# Microcontroller.net
KiCad netlist of a schematic drawn in Altium Designer
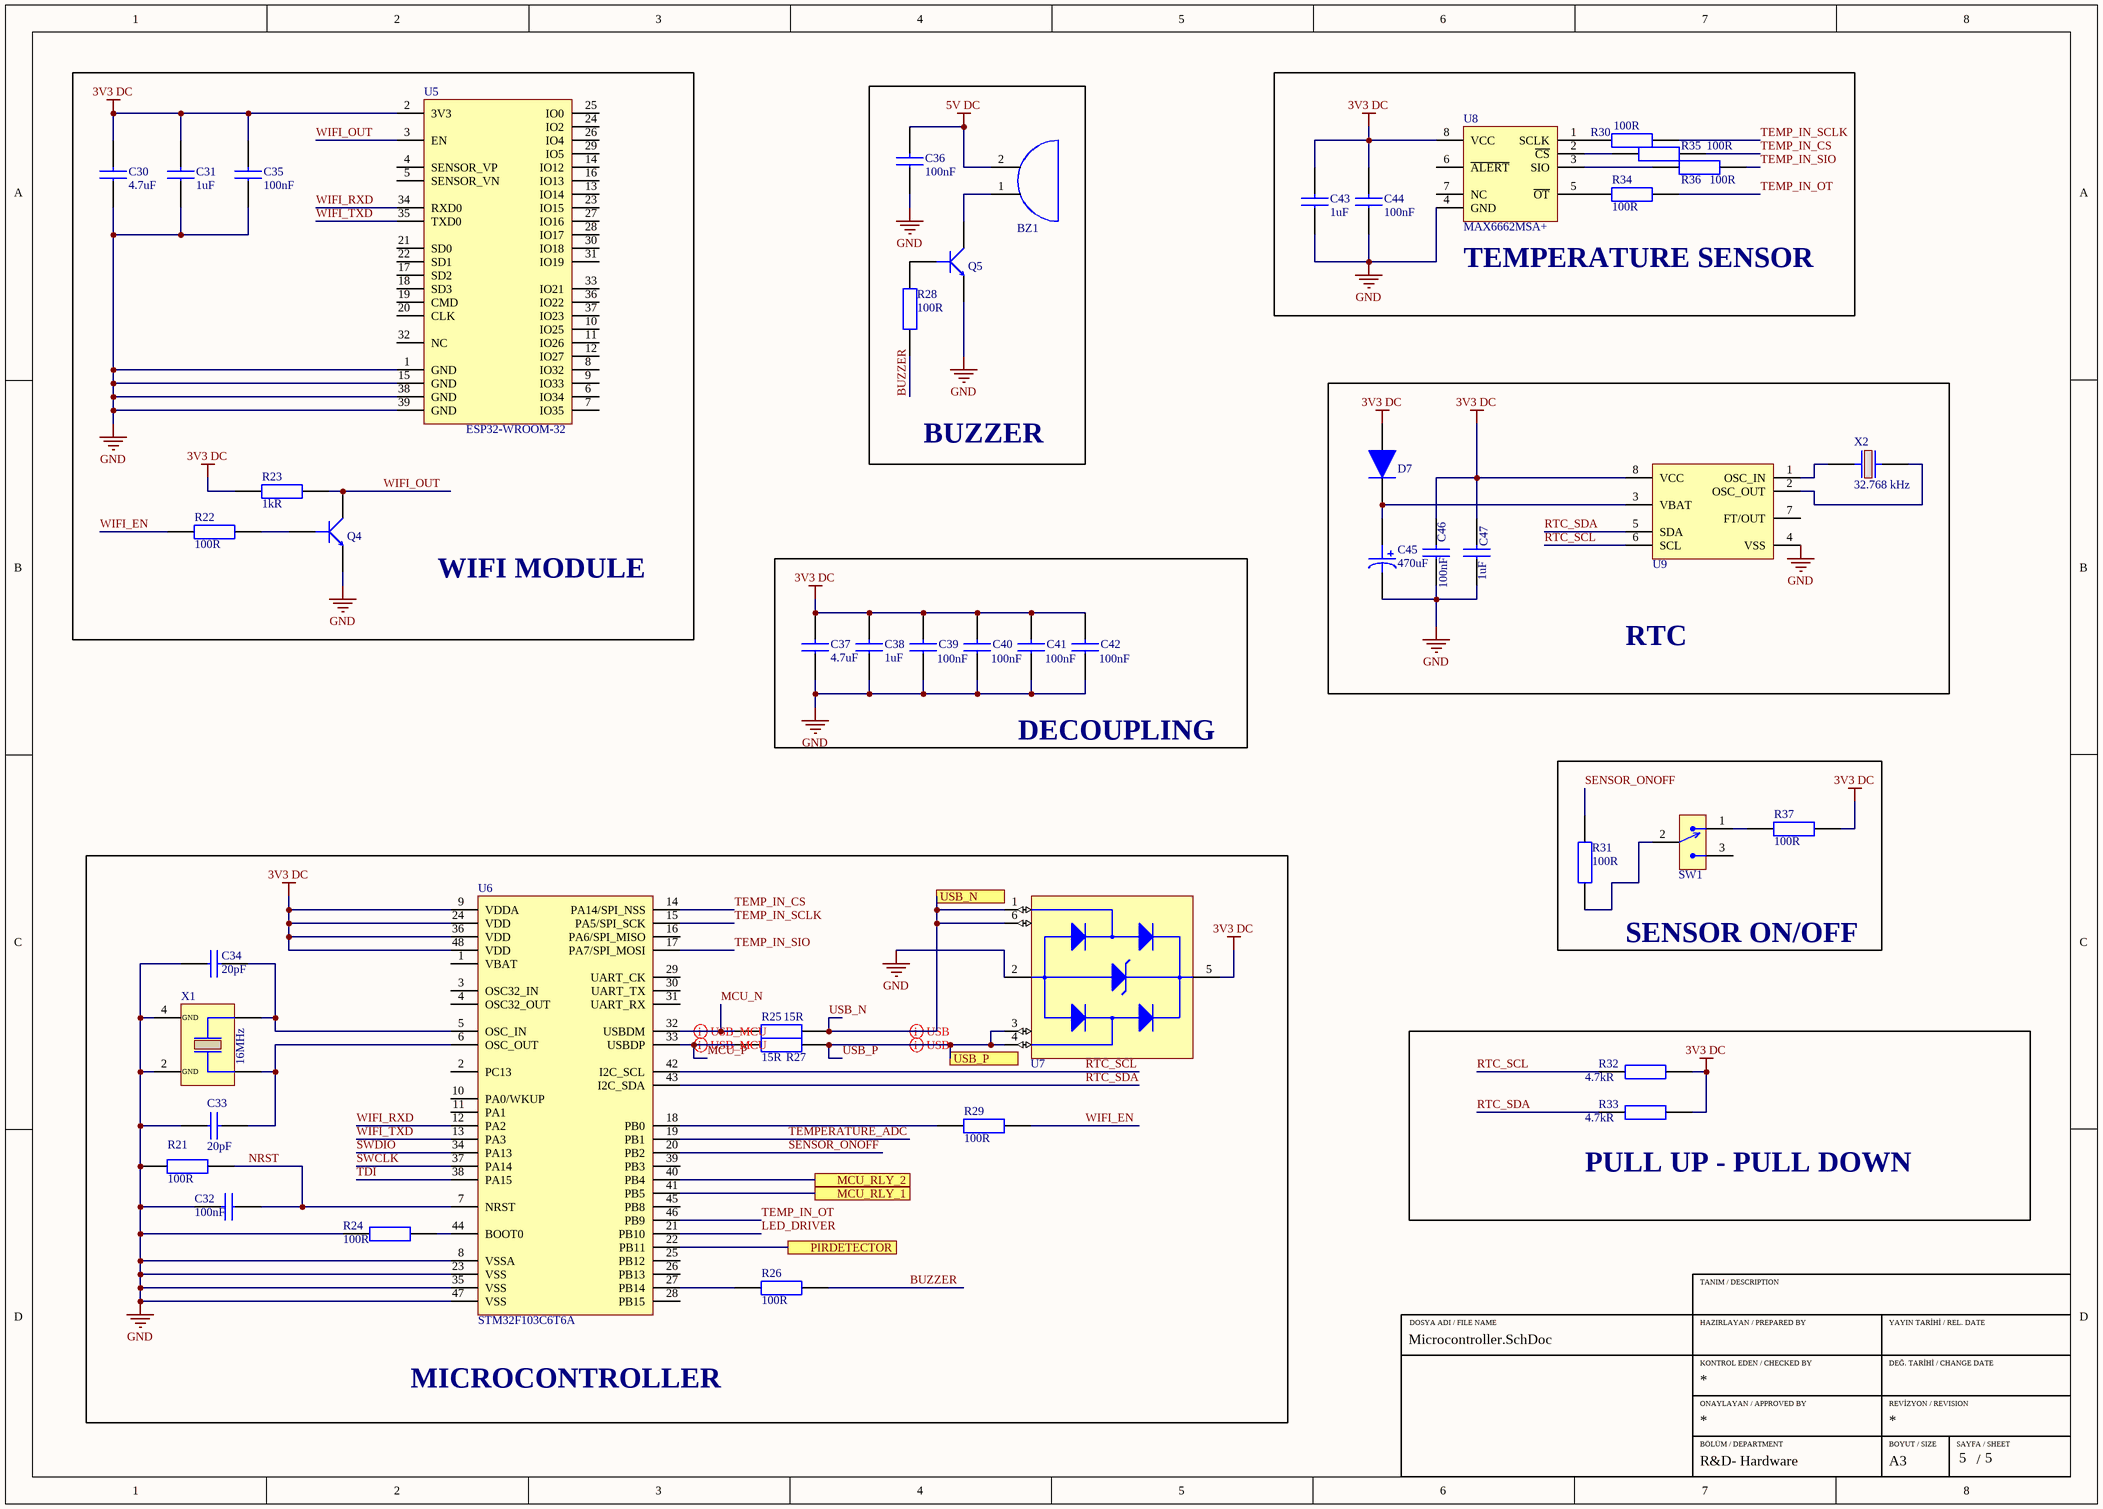
[diagram p0: Microcontroller.SchDoc]

(export (version "E")
  (design (tool "Eeschema 10.0.6"))
  (components
    (comp (ref "BZ1")
      (value "CMI-9605IC-0580T")
      (footprint "CMI-9605IC")
      (description "Buzzers Indicator, Internally Driven Magnetic 5V 30mA 2.7kHz 80dB @ 5V, 10cm Through Hole PC Pins")
      (fields (field (name "MANUFACTURER") "CUI Devices") (field (name "DESIGNED BY") "Kağan"))
      (libsource (lib "Udemy_Library") (part "CMI-9605IC-0580T_1"))
    )
    (comp (ref "C30")
      (value "CL21A475KAQNNNE")
      (footprint "CAP_0805")
      (description "CAP CER 4.7uF %10 0805")
      (fields
        (field (name "MANUFACTURER") "Samsung")
        (field (name "TOLERANCE") "10%")
        (field (name "CAPACITANCE") "4.7uF")
        (field (name "DESIGNED BY") "Kağan")
      )
      (libsource (lib "Udemy_Library") (part "CAP CER 4.7uF 0805"))
    )
    (comp (ref "C31")
      (value "CL21B105KBFNNNE")
      (footprint "CAP_0805")
      (description "CAP CER 1uF %10 0805")
      (fields
        (field (name "MANUFACTURER") "Samsung")
        (field (name "TOLERANCE") "10%")
        (field (name "CAPACITANCE") "1uF")
        (field (name "DESIGNED BY") "Kağan")
      )
      (libsource (lib "Udemy_Library") (part "CAP CER 1uF 0805"))
    )
    (comp (ref "C32")
      (value "CL21B104KBCNNNC")
      (footprint "CAP_0805")
      (description "CAP CER 100nF %10 0805")
      (fields
        (field (name "MANUFACTURER") "Samsung")
        (field (name "TOLERANCE") "10%")
        (field (name "CAPACITANCE") "100nF")
        (field (name "DESIGNED BY") "Kağan")
      )
      (libsource (lib "Udemy_Library") (part "CAP CER 100nF 0805"))
    )
    (comp (ref "C33")
      (value "CL10C200JB8NNNC")
      (footprint "CAP_0603")
      (description "CAP CER 20pF %5 0603 SMD")
      (fields
        (field (name "MANUFACTURER") "Samsung")
        (field (name "TOLERANCE") "5%")
        (field (name "CAPACITANCE") "20pF")
        (field (name "DESIGNED BY") "Kağan")
      )
      (libsource (lib "Udemy_Library") (part "CAP CER 20pF 0603"))
    )
    (comp (ref "C34")
      (value "CL10C200JB8NNNC")
      (footprint "CAP_0603")
      (description "CAP CER 20pF %5 0603 SMD")
      (fields
        (field (name "MANUFACTURER") "Samsung")
        (field (name "TOLERANCE") "5%")
        (field (name "CAPACITANCE") "20pF")
        (field (name "DESIGNED BY") "Kağan")
      )
      (libsource (lib "Udemy_Library") (part "CAP CER 20pF 0603"))
    )
    (comp (ref "C35")
      (value "CL21B104KBCNNNC")
      (footprint "CAP_0805")
      (description "CAP CER 100nF %10 0805")
      (fields
        (field (name "MANUFACTURER") "Samsung")
        (field (name "TOLERANCE") "10%")
        (field (name "CAPACITANCE") "100nF")
        (field (name "DESIGNED BY") "Kağan")
      )
      (libsource (lib "Udemy_Library") (part "CAP CER 100nF 0805"))
    )
    (comp (ref "C36")
      (value "CL21B104KBCNNNC")
      (footprint "CAP_0805")
      (description "CAP CER 100nF %10 0805")
      (fields
        (field (name "MANUFACTURER") "Samsung")
        (field (name "TOLERANCE") "10%")
        (field (name "CAPACITANCE") "100nF")
        (field (name "DESIGNED BY") "Kağan")
      )
      (libsource (lib "Udemy_Library") (part "CAP CER 100nF 0805"))
    )
    (comp (ref "C37")
      (value "CL21A475KAQNNNE")
      (footprint "CAP_0805")
      (description "CAP CER 4.7uF %10 0805")
      (fields
        (field (name "MANUFACTURER") "Samsung")
        (field (name "TOLERANCE") "10%")
        (field (name "CAPACITANCE") "4.7uF")
        (field (name "DESIGNED BY") "Kağan")
      )
      (libsource (lib "Udemy_Library") (part "CAP CER 4.7uF 0805"))
    )
    (comp (ref "C38")
      (value "CL21B105KBFNNNE")
      (footprint "CAP_0805")
      (description "CAP CER 1uF %10 0805")
      (fields
        (field (name "MANUFACTURER") "Samsung")
        (field (name "TOLERANCE") "10%")
        (field (name "CAPACITANCE") "1uF")
        (field (name "DESIGNED BY") "Kağan")
      )
      (libsource (lib "Udemy_Library") (part "CAP CER 1uF 0805"))
    )
    (comp (ref "C39")
      (value "CL21B104KBCNNNC")
      (footprint "CAP_0805")
      (description "CAP CER 100nF %10 0805")
      (fields
        (field (name "MANUFACTURER") "Samsung")
        (field (name "TOLERANCE") "10%")
        (field (name "CAPACITANCE") "100nF")
        (field (name "DESIGNED BY") "Kağan")
      )
      (libsource (lib "Udemy_Library") (part "CAP CER 100nF 0805"))
    )
    (comp (ref "C40")
      (value "CL21B104KBCNNNC")
      (footprint "CAP_0805")
      (description "CAP CER 100nF %10 0805")
      (fields
        (field (name "MANUFACTURER") "Samsung")
        (field (name "TOLERANCE") "10%")
        (field (name "CAPACITANCE") "100nF")
        (field (name "DESIGNED BY") "Kağan")
      )
      (libsource (lib "Udemy_Library") (part "CAP CER 100nF 0805"))
    )
    (comp (ref "C41")
      (value "CL21B104KBCNNNC")
      (footprint "CAP_0805")
      (description "CAP CER 100nF %10 0805")
      (fields
        (field (name "MANUFACTURER") "Samsung")
        (field (name "TOLERANCE") "10%")
        (field (name "CAPACITANCE") "100nF")
        (field (name "DESIGNED BY") "Kağan")
      )
      (libsource (lib "Udemy_Library") (part "CAP CER 100nF 0805"))
    )
    (comp (ref "C42")
      (value "CL21B104KBCNNNC")
      (footprint "CAP_0805")
      (description "CAP CER 100nF %10 0805")
      (fields
        (field (name "MANUFACTURER") "Samsung")
        (field (name "TOLERANCE") "10%")
        (field (name "CAPACITANCE") "100nF")
        (field (name "DESIGNED BY") "Kağan")
      )
      (libsource (lib "Udemy_Library") (part "CAP CER 100nF 0805"))
    )
    (comp (ref "C43")
      (value "CL21B105KBFNNNE")
      (footprint "CAP_0805")
      (description "CAP CER 1uF %10 0805")
      (fields
        (field (name "MANUFACTURER") "Samsung")
        (field (name "TOLERANCE") "10%")
        (field (name "CAPACITANCE") "1uF")
        (field (name "DESIGNED BY") "Kağan")
      )
      (libsource (lib "Udemy_Library") (part "CAP CER 1uF 0805"))
    )
    (comp (ref "C44")
      (value "CL21B104KBCNNNC")
      (footprint "CAP_0805")
      (description "CAP CER 100nF %10 0805")
      (fields
        (field (name "MANUFACTURER") "Samsung")
        (field (name "TOLERANCE") "10%")
        (field (name "CAPACITANCE") "100nF")
        (field (name "DESIGNED BY") "Kağan")
      )
      (libsource (lib "Udemy_Library") (part "CAP CER 100nF 0805"))
    )
    (comp (ref "C45")
      (value "ESH477M050AH4AA")
      (footprint "CAP_RADIAL_D10_P5 - duplicate")
      (description "CAP ALU ELEC 470uF 50V RADIAL")
      (fields
        (field (name "MANUFACTURER") "KEMET")
        (field (name "TOLERANCE") "20%")
        (field (name "CAPACITANCE") "470uF")
        (field (name "DESIGNED BY") "Kağan")
      )
      (libsource (lib "Udemy_Library") (part "CAP ALU ELEC 470uF 50V"))
    )
    (comp (ref "C46")
      (value "CL21B104KBCNNNC")
      (footprint "CAP_0805")
      (description "CAP CER 100nF %10 0805")
      (fields
        (field (name "MANUFACTURER") "Samsung")
        (field (name "TOLERANCE") "10%")
        (field (name "CAPACITANCE") "100nF")
        (field (name "DESIGNED BY") "Kağan")
      )
      (libsource (lib "Udemy_Library") (part "CAP CER 100nF 0805"))
    )
    (comp (ref "C47")
      (value "CL21B105KBFNNNE")
      (footprint "CAP_0805")
      (description "CAP CER 1uF %10 0805")
      (fields
        (field (name "MANUFACTURER") "Samsung")
        (field (name "TOLERANCE") "10%")
        (field (name "CAPACITANCE") "1uF")
        (field (name "DESIGNED BY") "Kağan")
      )
      (libsource (lib "Udemy_Library") (part "CAP CER 1uF 0805"))
    )
    (comp (ref "D7")
      (value "1N4148WS")
      (footprint "SOD323F")
      (description "Diode, Single, 75 V, 150 mA, 1 V, 4 ns")
      (fields
        (field (name "MANUFACTURER") "ON Semiconductor / Fairchild")
        (field (name "DESIGNED BY") "Kağan")
      )
      (libsource (lib "Udemy_Library") (part "1N4148WS"))
    )
    (comp (ref "Q4")
      (value "MMBT3904-7-F")
      (footprint "SOT-23F")
      (description "Transistor General Purpose BJT NPN 40 Volt 0.2A Automotive 3-Pin SOT-23")
      (fields (field (name "MANUFACTURER") "Diodes Zetex") (field (name "DESIGNED BY") "Kağan"))
      (libsource (lib "Udemy_Library") (part "MMBT3904-7-F"))
    )
    (comp (ref "Q5")
      (value "MMBT3904-7-F")
      (footprint "SOT-23F")
      (description "Transistor General Purpose BJT NPN 40 Volt 0.2A Automotive 3-Pin SOT-23")
      (fields (field (name "MANUFACTURER") "Diodes Zetex") (field (name "DESIGNED BY") "Kağan"))
      (libsource (lib "Udemy_Library") (part "MMBT3904-7-F"))
    )
    (comp (ref "R21")
      (value "RC0603JR-07100RL")
      (footprint "RES_0603")
      (description "RES 100 %5 OHM 0603 SMD")
      (fields
        (field (name "MANUFACTURER") "Yageo")
        (field (name "TOLERANCE") "5%")
        (field (name "RESISTANCE") "100R")
        (field (name "DESIGNED BY") "Kağan")
      )
      (libsource (lib "Udemy_Library") (part "RES 100 OHM 0603"))
    )
    (comp (ref "R22")
      (value "RC0603JR-07100RL")
      (footprint "RES_0603")
      (description "RES 100 %5 OHM 0603 SMD")
      (fields
        (field (name "MANUFACTURER") "Yageo")
        (field (name "TOLERANCE") "5%")
        (field (name "RESISTANCE") "100R")
        (field (name "DESIGNED BY") "Kağan")
      )
      (libsource (lib "") (part "RES 100 OHM 0603_1"))
    )
    (comp (ref "R23")
      (value "RC0603FR-0710KL")
      (footprint "RES_0603")
      (description "RES 1K %1 OHM 0603 SMD")
      (fields
        (field (name "MANUFACTURER") "Yageo")
        (field (name "MANUFACTURER PART NUMBER") "RC0603JR-071KL")
        (field (name "RESISTANCE") "1kR")
        (field (name "DESIGNED BY") "Kağan")
      )
      (libsource (lib "Udemy_Library") (part "RES 1K OHM 0603"))
    )
    (comp (ref "R24")
      (value "RC0603JR-07100RL")
      (footprint "RES_0603")
      (description "RES 100 %5 OHM 0603 SMD")
      (fields
        (field (name "MANUFACTURER") "Yageo")
        (field (name "TOLERANCE") "5%")
        (field (name "RESISTANCE") "100R")
        (field (name "DESIGNED BY") "Kağan")
      )
      (libsource (lib "Udemy_Library") (part "RES 100 OHM 0603"))
    )
    (comp (ref "R25")
      (value "RC0603JR-0715RL")
      (footprint "RES_0603")
      (description "RES 15 %5 OHM 0603 SMD")
      (fields
        (field (name "MANUFACTURER") "Yageo")
        (field (name "TOLERANCE") "5%")
        (field (name "RESISTANCE") "15R")
        (field (name "DESIGNED BY") "Kağan")
      )
      (libsource (lib "Udemy_Library") (part "RES 15 OHM 0603"))
    )
    (comp (ref "R26")
      (value "RC0603JR-07100RL")
      (footprint "RES_0603")
      (description "RES 100 %5 OHM 0603 SMD")
      (fields
        (field (name "MANUFACTURER") "Yageo")
        (field (name "TOLERANCE") "5%")
        (field (name "RESISTANCE") "100R")
        (field (name "DESIGNED BY") "Kağan")
      )
      (libsource (lib "Udemy_Library") (part "RES 100 OHM 0603"))
    )
    (comp (ref "R27")
      (value "RC0603JR-0715RL")
      (footprint "RES_0603")
      (description "RES 15 %5 OHM 0603 SMD")
      (fields
        (field (name "MANUFACTURER") "Yageo")
        (field (name "TOLERANCE") "5%")
        (field (name "RESISTANCE") "15R")
        (field (name "DESIGNED BY") "Kağan")
      )
      (libsource (lib "Udemy_Library") (part "RES 15 OHM 0603"))
    )
    (comp (ref "R28")
      (value "RC0603JR-07100RL")
      (footprint "RES_0603")
      (description "RES 100 %5 OHM 0603 SMD")
      (fields
        (field (name "MANUFACTURER") "Yageo")
        (field (name "TOLERANCE") "5%")
        (field (name "RESISTANCE") "100R")
        (field (name "DESIGNED BY") "Kağan")
      )
      (libsource (lib "") (part "RES 100 OHM 0603_2"))
    )
    (comp (ref "R29")
      (value "RC0603JR-07100RL")
      (footprint "RES_0603")
      (description "RES 100 %5 OHM 0603 SMD")
      (fields
        (field (name "MANUFACTURER") "Yageo")
        (field (name "TOLERANCE") "5%")
        (field (name "RESISTANCE") "100R")
        (field (name "DESIGNED BY") "Kağan")
      )
      (libsource (lib "Udemy_Library") (part "RES 100 OHM 0603"))
    )
    (comp (ref "R30")
      (value "RC0603JR-07100RL")
      (footprint "RES_0603")
      (description "RES 100 %5 OHM 0603 SMD")
      (fields
        (field (name "MANUFACTURER") "Yageo")
        (field (name "TOLERANCE") "5%")
        (field (name "RESISTANCE") "100R")
        (field (name "DESIGNED BY") "Kağan")
      )
      (libsource (lib "") (part "RES 100 OHM 0603_1"))
    )
    (comp (ref "R31")
      (value "RC0603JR-07100RL")
      (footprint "RES_0603")
      (description "RES 100 %5 OHM 0603 SMD")
      (fields
        (field (name "MANUFACTURER") "Yageo")
        (field (name "TOLERANCE") "5%")
        (field (name "RESISTANCE") "100R")
        (field (name "DESIGNED BY") "Kağan")
      )
      (libsource (lib "") (part "RES 100 OHM 0603_2"))
    )
    (comp (ref "R32")
      (value "RC0603JR-074K7L")
      (footprint "RES_0603")
      (description "RES 4K7 %5 OHM 0603 SMD")
      (fields
        (field (name "MANUFACTURER") "Yageo")
        (field (name "TOLERANCE") "5%")
        (field (name "RESISTANCE") "4.7kR")
        (field (name "DESIGNED BY") "Kağan")
      )
      (libsource (lib "Udemy_Library") (part "RES 4K7 OHM 0603"))
    )
    (comp (ref "R33")
      (value "RC0603JR-074K7L")
      (footprint "RES_0603")
      (description "RES 4K7 %5 OHM 0603 SMD")
      (fields
        (field (name "MANUFACTURER") "Yageo")
        (field (name "TOLERANCE") "5%")
        (field (name "RESISTANCE") "4.7kR")
        (field (name "DESIGNED BY") "Kağan")
      )
      (libsource (lib "Udemy_Library") (part "RES 4K7 OHM 0603"))
    )
    (comp (ref "R34")
      (value "RC0603JR-07100RL")
      (footprint "RES_0603")
      (description "RES 100 %5 OHM 0603 SMD")
      (fields
        (field (name "MANUFACTURER") "Yageo")
        (field (name "TOLERANCE") "5%")
        (field (name "RESISTANCE") "100R")
        (field (name "DESIGNED BY") "Kağan")
      )
      (libsource (lib "") (part "RES 100 OHM 0603_1"))
    )
    (comp (ref "R35")
      (value "RC0603JR-07100RL")
      (footprint "RES_0603")
      (description "RES 100 %5 OHM 0603 SMD")
      (fields
        (field (name "MANUFACTURER") "Yageo")
        (field (name "TOLERANCE") "5%")
        (field (name "RESISTANCE") "100R")
        (field (name "DESIGNED BY") "Kağan")
      )
      (libsource (lib "") (part "RES 100 OHM 0603_1"))
    )
    (comp (ref "R36")
      (value "RC0603JR-07100RL")
      (footprint "RES_0603")
      (description "RES 100 %5 OHM 0603 SMD")
      (fields
        (field (name "MANUFACTURER") "Yageo")
        (field (name "TOLERANCE") "5%")
        (field (name "RESISTANCE") "100R")
        (field (name "DESIGNED BY") "Kağan")
      )
      (libsource (lib "") (part "RES 100 OHM 0603_1"))
    )
    (comp (ref "R37")
      (value "RC0603JR-07100RL")
      (footprint "RES_0603")
      (description "RES 100 %5 OHM 0603 SMD")
      (fields
        (field (name "MANUFACTURER") "Yageo")
        (field (name "TOLERANCE") "5%")
        (field (name "RESISTANCE") "100R")
        (field (name "DESIGNED BY") "Kağan")
      )
      (libsource (lib "") (part "RES 100 OHM 0603_1"))
    )
    (comp (ref "SW1")
      (value "EG1215AA")
      (footprint "EG1215AA")
      (description "Slide Switch, SPDT, 0.025A, 24V, SMD")
      (fields
        (field (name "MANUFACTURER") "E-Switch")
        (field (name "TOLERANCE") "4.95%")
        (field (name "DESIGNED BY") "Kağan")
      )
      (libsource (lib "Udemy_Library") (part "EG1215AA"))
    )
    (comp (ref "U5")
      (value "ESP32-WROOM-32")
      (footprint "ESP32-32")
      (description "SMD MODULE, ESP32-D0WDQ6, 32MBIT")
      (fields (field (name "MANUFACTURER") "Espressif Systems") (field (name "DESIGNED BY") "Kağan"))
      (libsource (lib "Udemy_Library") (part "ESP32-WROOM-32_1"))
    )
    (comp (ref "U6")
      (value "STM32F103C6T6A")
      (footprint "LQFP48")
      (description "MCU 32-bit STM32F ARM Cortex M3 RISC 32KB Flash 2.5V/3.3V 48-Pin LQFP Tray")
      (fields (field (name "MANUFACTURER") "STMicroelectronics") (field (name "DESIGNED BY") "Kağan"))
      (libsource (lib "Udemy_Library") (part "STM32F103C6T6A"))
    )
    (comp (ref "U7")
      (value "USBLC6-2SC6")
      (footprint "SOT23-6L")
      (description "TVS DIODE 5.25V 17V SOT23-6")
      (fields (field (name "MANUFACTURER") "STMicroelectronics") (field (name "DESIGNED BY") "Kağan"))
      (libsource (lib "Udemy_Library") (part "USB PROTECTION"))
    )
    (comp (ref "U8")
      (value "MAX6662MSA+")
      (footprint "SOIC8")
      (description "Temp Sensor Digital Serial (3-Wire, SPI) 8-Pin SOIC N Tube")
      (fields (field (name "MANUFACTURER") "Maxim") (field (name "DESIGNED BY") "Kağan"))
      (libsource (lib "Udemy_Library") (part "MAX6662MSA+"))
    )
    (comp (ref "U9")
      (value "M41T100M6F")
      (footprint "SOIC8")
      (description "Real-time Clocks Clock/Calendar I2C, 2-Wire Serial 70uA @ 2V ~ 5.5V SOIC-8_150mil RoHS")
      (fields
        (field (name "MANUFACTURER") "STMicroelectronics")
        (field (name "MANUFACTURER PART NUMBER") "M41T00M6F")
        (field (name "DESIGNED BY") "Kağan")
      )
      (libsource (lib "Udemy_Library") (part "M41T00M6F"))
    )
    (comp (ref "X1")
      (value "ECS-160-20-30B-TR")
      (footprint "ECS")
      (description "CRYSTAL 16.0000MHZ 20PF SMD")
      (fields
        (field (name "MANUFACTURER") "ECS International")
        (field (name "TOLERANCE") "50ppm")
        (field (name "FREQUENCY") "16MHz")
        (field (name "DESIGNED BY") "Kağan")
      )
      (libsource (lib "Udemy_Library") (part "CRYSTAL 16MHz"))
    )
    (comp (ref "X2")
      (value "ABS05-32.768KHZ-T")
      (footprint "ABS05")
      (description "Crystal, 32.768 kHz, SMD, 1.6mm x 1mm, 12.5 pF, 20 ppm, ABS05 Series")
      (fields
        (field (name "MANUFACTURER") "Abracon")
        (field (name "TOLERANCE") "20ppm")
        (field (name "OPERATING FREQUENCY") "32.768 kHz")
        (field (name "DESIGNED BY") "Kağan")
      )
      (libsource (lib "Udemy_Library") (part "CRYSTAL 32768kHZ"))
    )
  )
  (nets
    (net (code "1") (name "/BUZZER") (class "Default")
      (node (ref "R26") (pin "2") (pinfunction "2_2") (pintype "passive"))
      (node (ref "R28") (pin "1") (pinfunction "1_1") (pintype "passive"))
    )
    (net (code "2") (name "/LED_DRIVER") (class "Default")
      (node (ref "U6") (pin "21") (pinfunction "PB10_21") (pintype "passive"))
    )
    (net (code "3") (name "/MCU_N") (class "Default")
      (node (ref "R25") (pin "1") (pinfunction "1_1") (pintype "passive"))
      (node (ref "U6") (pin "32") (pinfunction "USBDM_32") (pintype "passive"))
    )
    (net (code "4") (name "/MCU_P") (class "Default")
      (node (ref "R27") (pin "1") (pinfunction "1_1") (pintype "passive"))
      (node (ref "U6") (pin "33") (pinfunction "USBDP_33") (pintype "passive"))
    )
    (net (code "5") (name "/MCU_RLY_1") (class "Default")
      (node (ref "U6") (pin "41") (pinfunction "PB5_41") (pintype "passive"))
    )
    (net (code "6") (name "/MCU_RLY_2") (class "Default")
      (node (ref "U6") (pin "40") (pinfunction "PB4_40") (pintype "passive"))
    )
    (net (code "7") (name "/NRST") (class "Default")
      (node (ref "C32") (pin "1") (pinfunction "1_1") (pintype "passive"))
      (node (ref "R21") (pin "2") (pinfunction "2_2") (pintype "passive"))
      (node (ref "U6") (pin "7") (pinfunction "NRST_7") (pintype "passive"))
    )
    (net (code "8") (name "/PIRDETECTOR") (class "Default")
      (node (ref "U6") (pin "22") (pinfunction "PB11_22") (pintype "passive"))
    )
    (net (code "9") (name "/RTC_SCL") (class "Default")
      (node (ref "R32") (pin "1") (pinfunction "1_1") (pintype "passive"))
      (node (ref "U6") (pin "42") (pinfunction "I2C_SCL_42") (pintype "passive"))
      (node (ref "U9") (pin "6") (pinfunction "SCL_6") (pintype "passive"))
    )
    (net (code "10") (name "/RTC_SDA") (class "Default")
      (node (ref "R33") (pin "1") (pinfunction "1_1") (pintype "passive"))
      (node (ref "U6") (pin "43") (pinfunction "I2C_SDA_43") (pintype "passive"))
      (node (ref "U9") (pin "5") (pinfunction "SDA_5") (pintype "passive"))
    )
    (net (code "11") (name "/SENSOR_ONOFF") (class "Default")
      (node (ref "R31") (pin "2") (pinfunction "2_2") (pintype "passive"))
      (node (ref "U6") (pin "20") (pinfunction "PB2_20") (pintype "passive"))
    )
    (net (code "12") (name "/SWCLK") (class "Default")
      (node (ref "U6") (pin "37") (pinfunction "PA14_37") (pintype "passive"))
    )
    (net (code "13") (name "/SWDIO") (class "Default")
      (node (ref "U6") (pin "34") (pinfunction "PA13_34") (pintype "passive"))
    )
    (net (code "14") (name "/TDI") (class "Default")
      (node (ref "U6") (pin "38") (pinfunction "PA15_38") (pintype "passive"))
    )
    (net (code "15") (name "/TEMPERATURE_ADC") (class "Default")
      (node (ref "U6") (pin "19") (pinfunction "PB1_19") (pintype "passive"))
    )
    (net (code "16") (name "/TEMP_IN_CS") (class "Default")
      (node (ref "R35") (pin "1") (pinfunction "1_1") (pintype "passive"))
      (node (ref "U6") (pin "14") (pinfunction "PA14/SPI_NSS_14") (pintype "passive"))
    )
    (net (code "17") (name "/TEMP_IN_OT") (class "Default")
      (node (ref "R34") (pin "1") (pinfunction "1_1") (pintype "passive"))
      (node (ref "U6") (pin "46") (pinfunction "PB9_46") (pintype "passive"))
    )
    (net (code "18") (name "/TEMP_IN_SCLK") (class "Default")
      (node (ref "R30") (pin "1") (pinfunction "1_1") (pintype "passive"))
      (node (ref "U6") (pin "15") (pinfunction "PA5/SPI_SCK_15") (pintype "passive"))
    )
    (net (code "19") (name "/TEMP_IN_SIO") (class "Default")
      (node (ref "R36") (pin "1") (pinfunction "1_1") (pintype "passive"))
      (node (ref "U6") (pin "17") (pinfunction "PA7/SPI_MOSI_17") (pintype "passive"))
    )
    (net (code "20") (name "/USB_N") (class "Default")
      (node (ref "R25") (pin "2") (pinfunction "2_2") (pintype "passive"))
      (node (ref "U7") (pin "1") (pinfunction "I/O1_1") (pintype "bidirectional"))
      (node (ref "U7") (pin "6") (pinfunction "I/O1_6") (pintype "bidirectional"))
    )
    (net (code "21") (name "/USB_P") (class "Default")
      (node (ref "R27") (pin "2") (pinfunction "2_2") (pintype "passive"))
      (node (ref "U7") (pin "3") (pinfunction "I/O2_3") (pintype "bidirectional"))
      (node (ref "U7") (pin "4") (pinfunction "I/O2_4") (pintype "bidirectional"))
    )
    (net (code "22") (name "/WIFI_EN") (class "Default")
      (node (ref "R22") (pin "2") (pinfunction "2_2") (pintype "passive"))
      (node (ref "R29") (pin "2") (pinfunction "2_2") (pintype "passive"))
    )
    (net (code "23") (name "/WIFI_OUT") (class "Default")
      (node (ref "Q4") (pin "3") (pinfunction "C_3") (pintype "power_in"))
      (node (ref "R23") (pin "2") (pinfunction "2_2") (pintype "passive"))
      (node (ref "U5") (pin "3") (pinfunction "EN_3") (pintype "passive"))
    )
    (net (code "24") (name "/WIFI_RXD") (class "Default")
      (node (ref "U5") (pin "34") (pinfunction "RXD0_34") (pintype "passive"))
      (node (ref "U6") (pin "12") (pinfunction "PA2_12") (pintype "passive"))
    )
    (net (code "25") (name "/WIFI_TXD") (class "Default")
      (node (ref "U5") (pin "35") (pinfunction "TXD0_35") (pintype "passive"))
      (node (ref "U6") (pin "13") (pinfunction "PA3_13") (pintype "passive"))
    )
    (net (code "26") (name "3V3 DC") (class "Default")
      (node (ref "C30") (pin "2") (pinfunction "2_2") (pintype "passive"))
      (node (ref "C31") (pin "2") (pinfunction "2_2") (pintype "passive"))
      (node (ref "C35") (pin "2") (pinfunction "2_2") (pintype "passive"))
      (node (ref "C37") (pin "2") (pinfunction "2_2") (pintype "passive"))
      (node (ref "C38") (pin "2") (pinfunction "2_2") (pintype "passive"))
      (node (ref "C39") (pin "2") (pinfunction "2_2") (pintype "passive"))
      (node (ref "C40") (pin "2") (pinfunction "2_2") (pintype "passive"))
      (node (ref "C41") (pin "2") (pinfunction "2_2") (pintype "passive"))
      (node (ref "C42") (pin "2") (pinfunction "2_2") (pintype "passive"))
      (node (ref "C43") (pin "2") (pinfunction "2_2") (pintype "passive"))
      (node (ref "C44") (pin "2") (pinfunction "2_2") (pintype "passive"))
      (node (ref "C46") (pin "2") (pinfunction "2_2") (pintype "passive"))
      (node (ref "C47") (pin "2") (pinfunction "2_2") (pintype "passive"))
      (node (ref "D7") (pin "2") (pinfunction "2_2") (pintype "power_in"))
      (node (ref "R23") (pin "1") (pinfunction "1_1") (pintype "passive"))
      (node (ref "R32") (pin "2") (pinfunction "2_2") (pintype "passive"))
      (node (ref "R33") (pin "2") (pinfunction "2_2") (pintype "passive"))
      (node (ref "R37") (pin "1") (pinfunction "1_1") (pintype "passive"))
      (node (ref "U5") (pin "2") (pinfunction "3V3_2") (pintype "passive"))
      (node (ref "U6") (pin "24") (pinfunction "VDD_24") (pintype "passive"))
      (node (ref "U6") (pin "36") (pinfunction "VDD_36") (pintype "passive"))
      (node (ref "U6") (pin "48") (pinfunction "VDD_48") (pintype "passive"))
      (node (ref "U6") (pin "9") (pinfunction "VDDA_9") (pintype "passive"))
      (node (ref "U7") (pin "5") (pinfunction "VBUS_5") (pintype "power_in"))
      (node (ref "U8") (pin "8") (pinfunction "VCC_8") (pintype "passive"))
      (node (ref "U9") (pin "8") (pinfunction "VCC_8") (pintype "passive"))
    )
    (net (code "27") (name "5V DC") (class "Default")
      (node (ref "BZ1") (pin "2") (pinfunction "2_2") (pintype "passive"))
      (node (ref "C36") (pin "2") (pinfunction "2_2") (pintype "passive"))
    )
    (net (code "28") (name "GND") (class "Default")
      (node (ref "C30") (pin "1") (pinfunction "1_1") (pintype "passive"))
      (node (ref "C31") (pin "1") (pinfunction "1_1") (pintype "passive"))
      (node (ref "C32") (pin "2") (pinfunction "2_2") (pintype "passive"))
      (node (ref "C33") (pin "1") (pinfunction "1_1") (pintype "passive"))
      (node (ref "C34") (pin "1") (pinfunction "1_1") (pintype "passive"))
      (node (ref "C35") (pin "1") (pinfunction "1_1") (pintype "passive"))
      (node (ref "C36") (pin "1") (pinfunction "1_1") (pintype "passive"))
      (node (ref "C37") (pin "1") (pinfunction "1_1") (pintype "passive"))
      (node (ref "C38") (pin "1") (pinfunction "1_1") (pintype "passive"))
      (node (ref "C39") (pin "1") (pinfunction "1_1") (pintype "passive"))
      (node (ref "C40") (pin "1") (pinfunction "1_1") (pintype "passive"))
      (node (ref "C41") (pin "1") (pinfunction "1_1") (pintype "passive"))
      (node (ref "C42") (pin "1") (pinfunction "1_1") (pintype "passive"))
      (node (ref "C43") (pin "1") (pinfunction "1_1") (pintype "passive"))
      (node (ref "C44") (pin "1") (pinfunction "1_1") (pintype "passive"))
      (node (ref "C45") (pin "2") (pinfunction "2_2") (pintype "passive"))
      (node (ref "C46") (pin "1") (pinfunction "1_1") (pintype "passive"))
      (node (ref "C47") (pin "1") (pinfunction "1_1") (pintype "passive"))
      (node (ref "Q4") (pin "2") (pinfunction "E_2") (pintype "power_in"))
      (node (ref "Q5") (pin "2") (pinfunction "E_2") (pintype "power_in"))
      (node (ref "R21") (pin "1") (pinfunction "1_1") (pintype "passive"))
      (node (ref "R24") (pin "1") (pinfunction "1_1") (pintype "passive"))
      (node (ref "U5") (pin "1") (pinfunction "GND_1") (pintype "passive"))
      (node (ref "U5") (pin "15") (pinfunction "GND_15") (pintype "passive"))
      (node (ref "U5") (pin "38") (pinfunction "GND_38") (pintype "passive"))
      (node (ref "U5") (pin "39") (pinfunction "GND_39") (pintype "passive"))
      (node (ref "U6") (pin "23") (pinfunction "VSS_23") (pintype "passive"))
      (node (ref "U6") (pin "35") (pinfunction "VSS_35") (pintype "passive"))
      (node (ref "U6") (pin "47") (pinfunction "VSS_47") (pintype "passive"))
      (node (ref "U6") (pin "8") (pinfunction "VSSA_8") (pintype "passive"))
      (node (ref "U7") (pin "2") (pinfunction "GND_2") (pintype "power_in"))
      (node (ref "U8") (pin "4") (pinfunction "GND_4") (pintype "passive"))
      (node (ref "U9") (pin "4") (pinfunction "VSS_4") (pintype "passive"))
      (node (ref "X1") (pin "2") (pinfunction "GND_2") (pintype "passive"))
      (node (ref "X1") (pin "4") (pinfunction "GND_4") (pintype "passive"))
    )
    (net (code "29") (name "Net-(Q4-B)") (class "Default")
      (node (ref "Q4") (pin "1") (pinfunction "B_1") (pintype "power_in"))
      (node (ref "R22") (pin "1") (pinfunction "1_1") (pintype "passive"))
    )
    (net (code "30") (name "Net-(Q5-B)") (class "Default")
      (node (ref "Q5") (pin "1") (pinfunction "B_1") (pintype "power_in"))
      (node (ref "R28") (pin "2") (pinfunction "2_2") (pintype "passive"))
    )
    (net (code "31") (name "Net-(Q5-C)") (class "Default")
      (node (ref "BZ1") (pin "1") (pinfunction "1_1") (pintype "passive"))
      (node (ref "Q5") (pin "3") (pinfunction "C_3") (pintype "power_in"))
    )
    (net (code "32") (name "Net-(R31-Pad1)") (class "Default")
      (node (ref "R31") (pin "1") (pinfunction "1_1") (pintype "passive"))
      (node (ref "SW1") (pin "2") (pinfunction "2_2") (pintype "passive"))
    )
    (net (code "33") (name "Net-(R37-Pad2)") (class "Default")
      (node (ref "R37") (pin "2") (pinfunction "2_2") (pintype "passive"))
      (node (ref "SW1") (pin "1") (pinfunction "1_1") (pintype "passive"))
    )
    (net (code "34") (name "Net-(U6-BOOT0)") (class "Default")
      (node (ref "R24") (pin "2") (pinfunction "2_2") (pintype "passive"))
      (node (ref "U6") (pin "44") (pinfunction "BOOT0_44") (pintype "passive"))
    )
    (net (code "35") (name "Net-(U6-OSC_IN)") (class "Default")
      (node (ref "C34") (pin "2") (pinfunction "2_2") (pintype "passive"))
      (node (ref "U6") (pin "5") (pinfunction "OSC_IN_5") (pintype "passive"))
      (node (ref "X1") (pin "3") (pinfunction "3_3") (pintype "passive"))
    )
    (net (code "36") (name "Net-(U6-OSC_OUT)") (class "Default")
      (node (ref "C33") (pin "2") (pinfunction "2_2") (pintype "passive"))
      (node (ref "U6") (pin "6") (pinfunction "OSC_OUT_6") (pintype "passive"))
      (node (ref "X1") (pin "1") (pinfunction "1_1") (pintype "passive"))
    )
    (net (code "37") (name "Net-(U6-PB0)") (class "Default")
      (node (ref "R29") (pin "1") (pinfunction "1_1") (pintype "passive"))
      (node (ref "U6") (pin "18") (pinfunction "PB0_18") (pintype "passive"))
    )
    (net (code "38") (name "Net-(U6-PB14)") (class "Default")
      (node (ref "R26") (pin "1") (pinfunction "1_1") (pintype "passive"))
      (node (ref "U6") (pin "27") (pinfunction "PB14_27") (pintype "passive"))
    )
    (net (code "39") (name "Net-(U8-SCLK)") (class "Default")
      (node (ref "R30") (pin "2") (pinfunction "2_2") (pintype "passive"))
      (node (ref "U8") (pin "1") (pinfunction "SCLK_1") (pintype "passive"))
    )
    (net (code "40") (name "Net-(U8-SIO)") (class "Default")
      (node (ref "R36") (pin "2") (pinfunction "2_2") (pintype "passive"))
      (node (ref "U8") (pin "3") (pinfunction "SIO_3") (pintype "passive"))
    )
    (net (code "41") (name "Net-(U8-~{CS})") (class "Default")
      (node (ref "R35") (pin "2") (pinfunction "2_2") (pintype "passive"))
      (node (ref "U8") (pin "2") (pinfunction "~{CS}_2") (pintype "passive"))
    )
    (net (code "42") (name "Net-(U8-~{OT})") (class "Default")
      (node (ref "R34") (pin "2") (pinfunction "2_2") (pintype "passive"))
      (node (ref "U8") (pin "5") (pinfunction "~{OT}_5") (pintype "passive"))
    )
    (net (code "43") (name "Net-(U9-OSC_IN)") (class "Default")
      (node (ref "U9") (pin "1") (pinfunction "OSC_IN_1") (pintype "passive"))
      (node (ref "X2") (pin "2") (pinfunction "2_2") (pintype "passive"))
    )
    (net (code "44") (name "Net-(U9-OSC_OUT)") (class "Default")
      (node (ref "U9") (pin "2") (pinfunction "OSC_OUT_2") (pintype "passive"))
      (node (ref "X2") (pin "1") (pinfunction "1_1") (pintype "passive"))
    )
    (net (code "45") (name "Net-(U9-VBAT)") (class "Default")
      (node (ref "C45") (pin "1") (pinfunction "1_1") (pintype "passive"))
      (node (ref "D7") (pin "1") (pinfunction "1_1") (pintype "power_in"))
      (node (ref "U9") (pin "3") (pinfunction "VBAT_3") (pintype "passive"))
    )
    (net (code "46") (name "unconnected-(SW1-Pad3)") (class "Default")
      (node (ref "SW1") (pin "3") (pinfunction "3_3") (pintype "passive"))
    )
    (net (code "47") (name "unconnected-(U5-CLK-Pad20)") (class "Default")
      (node (ref "U5") (pin "20") (pinfunction "CLK_20") (pintype "passive"))
    )
    (net (code "48") (name "unconnected-(U5-CMD-Pad19)") (class "Default")
      (node (ref "U5") (pin "19") (pinfunction "CMD_19") (pintype "passive"))
    )
    (net (code "49") (name "unconnected-(U5-IO0-Pad25)") (class "Default")
      (node (ref "U5") (pin "25") (pinfunction "IO0_25") (pintype "passive"))
    )
    (net (code "50") (name "unconnected-(U5-IO2-Pad24)") (class "Default")
      (node (ref "U5") (pin "24") (pinfunction "IO2_24") (pintype "passive"))
    )
    (net (code "51") (name "unconnected-(U5-IO4-Pad26)") (class "Default")
      (node (ref "U5") (pin "26") (pinfunction "IO4_26") (pintype "passive"))
    )
    (net (code "52") (name "unconnected-(U5-IO5-Pad29)") (class "Default")
      (node (ref "U5") (pin "29") (pinfunction "IO5_29") (pintype "passive"))
    )
    (net (code "53") (name "unconnected-(U5-IO12-Pad14)") (class "Default")
      (node (ref "U5") (pin "14") (pinfunction "IO12_14") (pintype "passive"))
    )
    (net (code "54") (name "unconnected-(U5-IO13-Pad16)") (class "Default")
      (node (ref "U5") (pin "16") (pinfunction "IO13_16") (pintype "passive"))
    )
    (net (code "55") (name "unconnected-(U5-IO14-Pad13)") (class "Default")
      (node (ref "U5") (pin "13") (pinfunction "IO14_13") (pintype "passive"))
    )
    (net (code "56") (name "unconnected-(U5-IO15-Pad23)") (class "Default")
      (node (ref "U5") (pin "23") (pinfunction "IO15_23") (pintype "passive"))
    )
    (net (code "57") (name "unconnected-(U5-IO16-Pad27)") (class "Default")
      (node (ref "U5") (pin "27") (pinfunction "IO16_27") (pintype "passive"))
    )
    (net (code "58") (name "unconnected-(U5-IO17-Pad28)") (class "Default")
      (node (ref "U5") (pin "28") (pinfunction "IO17_28") (pintype "passive"))
    )
    (net (code "59") (name "unconnected-(U5-IO18-Pad30)") (class "Default")
      (node (ref "U5") (pin "30") (pinfunction "IO18_30") (pintype "passive"))
    )
    (net (code "60") (name "unconnected-(U5-IO19-Pad31)") (class "Default")
      (node (ref "U5") (pin "31") (pinfunction "IO19_31") (pintype "passive"))
    )
    (net (code "61") (name "unconnected-(U5-IO21-Pad33)") (class "Default")
      (node (ref "U5") (pin "33") (pinfunction "IO21_33") (pintype "passive"))
    )
    (net (code "62") (name "unconnected-(U5-IO22-Pad36)") (class "Default")
      (node (ref "U5") (pin "36") (pinfunction "IO22_36") (pintype "passive"))
    )
    (net (code "63") (name "unconnected-(U5-IO23-Pad37)") (class "Default")
      (node (ref "U5") (pin "37") (pinfunction "IO23_37") (pintype "passive"))
    )
    (net (code "64") (name "unconnected-(U5-IO25-Pad10)") (class "Default")
      (node (ref "U5") (pin "10") (pinfunction "IO25_10") (pintype "passive"))
    )
    (net (code "65") (name "unconnected-(U5-IO26-Pad11)") (class "Default")
      (node (ref "U5") (pin "11") (pinfunction "IO26_11") (pintype "passive"))
    )
    (net (code "66") (name "unconnected-(U5-IO27-Pad12)") (class "Default")
      (node (ref "U5") (pin "12") (pinfunction "IO27_12") (pintype "passive"))
    )
    (net (code "67") (name "unconnected-(U5-IO32-Pad8)") (class "Default")
      (node (ref "U5") (pin "8") (pinfunction "IO32_8") (pintype "passive"))
    )
    (net (code "68") (name "unconnected-(U5-IO33-Pad9)") (class "Default")
      (node (ref "U5") (pin "9") (pinfunction "IO33_9") (pintype "passive"))
    )
    (net (code "69") (name "unconnected-(U5-IO34-Pad6)") (class "Default")
      (node (ref "U5") (pin "6") (pinfunction "IO34_6") (pintype "passive"))
    )
    (net (code "70") (name "unconnected-(U5-IO35-Pad7)") (class "Default")
      (node (ref "U5") (pin "7") (pinfunction "IO35_7") (pintype "passive"))
    )
    (net (code "71") (name "unconnected-(U5-NC-Pad32)") (class "Default")
      (node (ref "U5") (pin "32") (pinfunction "NC_32") (pintype "passive"))
    )
    (net (code "72") (name "unconnected-(U5-SD0-Pad21)") (class "Default")
      (node (ref "U5") (pin "21") (pinfunction "SD0_21") (pintype "passive"))
    )
    (net (code "73") (name "unconnected-(U5-SD1-Pad22)") (class "Default")
      (node (ref "U5") (pin "22") (pinfunction "SD1_22") (pintype "passive"))
    )
    (net (code "74") (name "unconnected-(U5-SD2-Pad17)") (class "Default")
      (node (ref "U5") (pin "17") (pinfunction "SD2_17") (pintype "passive"))
    )
    (net (code "75") (name "unconnected-(U5-SD3-Pad18)") (class "Default")
      (node (ref "U5") (pin "18") (pinfunction "SD3_18") (pintype "passive"))
    )
    (net (code "76") (name "unconnected-(U5-SENSOR_VN-Pad5)") (class "Default")
      (node (ref "U5") (pin "5") (pinfunction "SENSOR_VN_5") (pintype "passive"))
    )
    (net (code "77") (name "unconnected-(U5-SENSOR_VP-Pad4)") (class "Default")
      (node (ref "U5") (pin "4") (pinfunction "SENSOR_VP_4") (pintype "passive"))
    )
    (net (code "78") (name "unconnected-(U6-OSC32_IN-Pad3)") (class "Default")
      (node (ref "U6") (pin "3") (pinfunction "OSC32_IN_3") (pintype "passive"))
    )
    (net (code "79") (name "unconnected-(U6-OSC32_OUT-Pad4)") (class "Default")
      (node (ref "U6") (pin "4") (pinfunction "OSC32_OUT_4") (pintype "passive"))
    )
    (net (code "80") (name "unconnected-(U6-PA0{slash}WKUP-Pad10)") (class "Default")
      (node (ref "U6") (pin "10") (pinfunction "PA0/WKUP_10") (pintype "passive"))
    )
    (net (code "81") (name "unconnected-(U6-PA1-Pad11)") (class "Default")
      (node (ref "U6") (pin "11") (pinfunction "PA1_11") (pintype "passive"))
    )
    (net (code "82") (name "unconnected-(U6-PA6{slash}SPI_MISO-Pad16)") (class "Default")
      (node (ref "U6") (pin "16") (pinfunction "PA6/SPI_MISO_16") (pintype "passive"))
    )
    (net (code "83") (name "unconnected-(U6-PB3-Pad39)") (class "Default")
      (node (ref "U6") (pin "39") (pinfunction "PB3_39") (pintype "passive"))
    )
    (net (code "84") (name "unconnected-(U6-PB8-Pad45)") (class "Default")
      (node (ref "U6") (pin "45") (pinfunction "PB8_45") (pintype "passive"))
    )
    (net (code "85") (name "unconnected-(U6-PB12-Pad25)") (class "Default")
      (node (ref "U6") (pin "25") (pinfunction "PB12_25") (pintype "passive"))
    )
    (net (code "86") (name "unconnected-(U6-PB13-Pad26)") (class "Default")
      (node (ref "U6") (pin "26") (pinfunction "PB13_26") (pintype "passive"))
    )
    (net (code "87") (name "unconnected-(U6-PB15-Pad28)") (class "Default")
      (node (ref "U6") (pin "28") (pinfunction "PB15_28") (pintype "passive"))
    )
    (net (code "88") (name "unconnected-(U6-PC13-Pad2)") (class "Default")
      (node (ref "U6") (pin "2") (pinfunction "PC13_2") (pintype "passive"))
    )
    (net (code "89") (name "unconnected-(U6-UART_CK-Pad29)") (class "Default")
      (node (ref "U6") (pin "29") (pinfunction "UART_CK_29") (pintype "passive"))
    )
    (net (code "90") (name "unconnected-(U6-UART_RX-Pad31)") (class "Default")
      (node (ref "U6") (pin "31") (pinfunction "UART_RX_31") (pintype "passive"))
    )
    (net (code "91") (name "unconnected-(U6-UART_TX-Pad30)") (class "Default")
      (node (ref "U6") (pin "30") (pinfunction "UART_TX_30") (pintype "passive"))
    )
    (net (code "92") (name "unconnected-(U6-VBAT-Pad1)") (class "Default")
      (node (ref "U6") (pin "1") (pinfunction "VBAT_1") (pintype "passive"))
    )
    (net (code "93") (name "unconnected-(U8-NC-Pad7)") (class "Default")
      (node (ref "U8") (pin "7") (pinfunction "NC_7") (pintype "passive"))
    )
    (net (code "94") (name "unconnected-(U8-~{ALERT}-Pad6)") (class "Default")
      (node (ref "U8") (pin "6") (pinfunction "~{ALERT}_6") (pintype "passive"))
    )
    (net (code "95") (name "unconnected-(U9-FT{slash}OUT-Pad7)") (class "Default")
      (node (ref "U9") (pin "7") (pinfunction "FT/OUT_7") (pintype "passive"))
    )
  )
)
